# as14120_x31_usb.net
KiCad netlist of a schematic drawn in Altium Designer
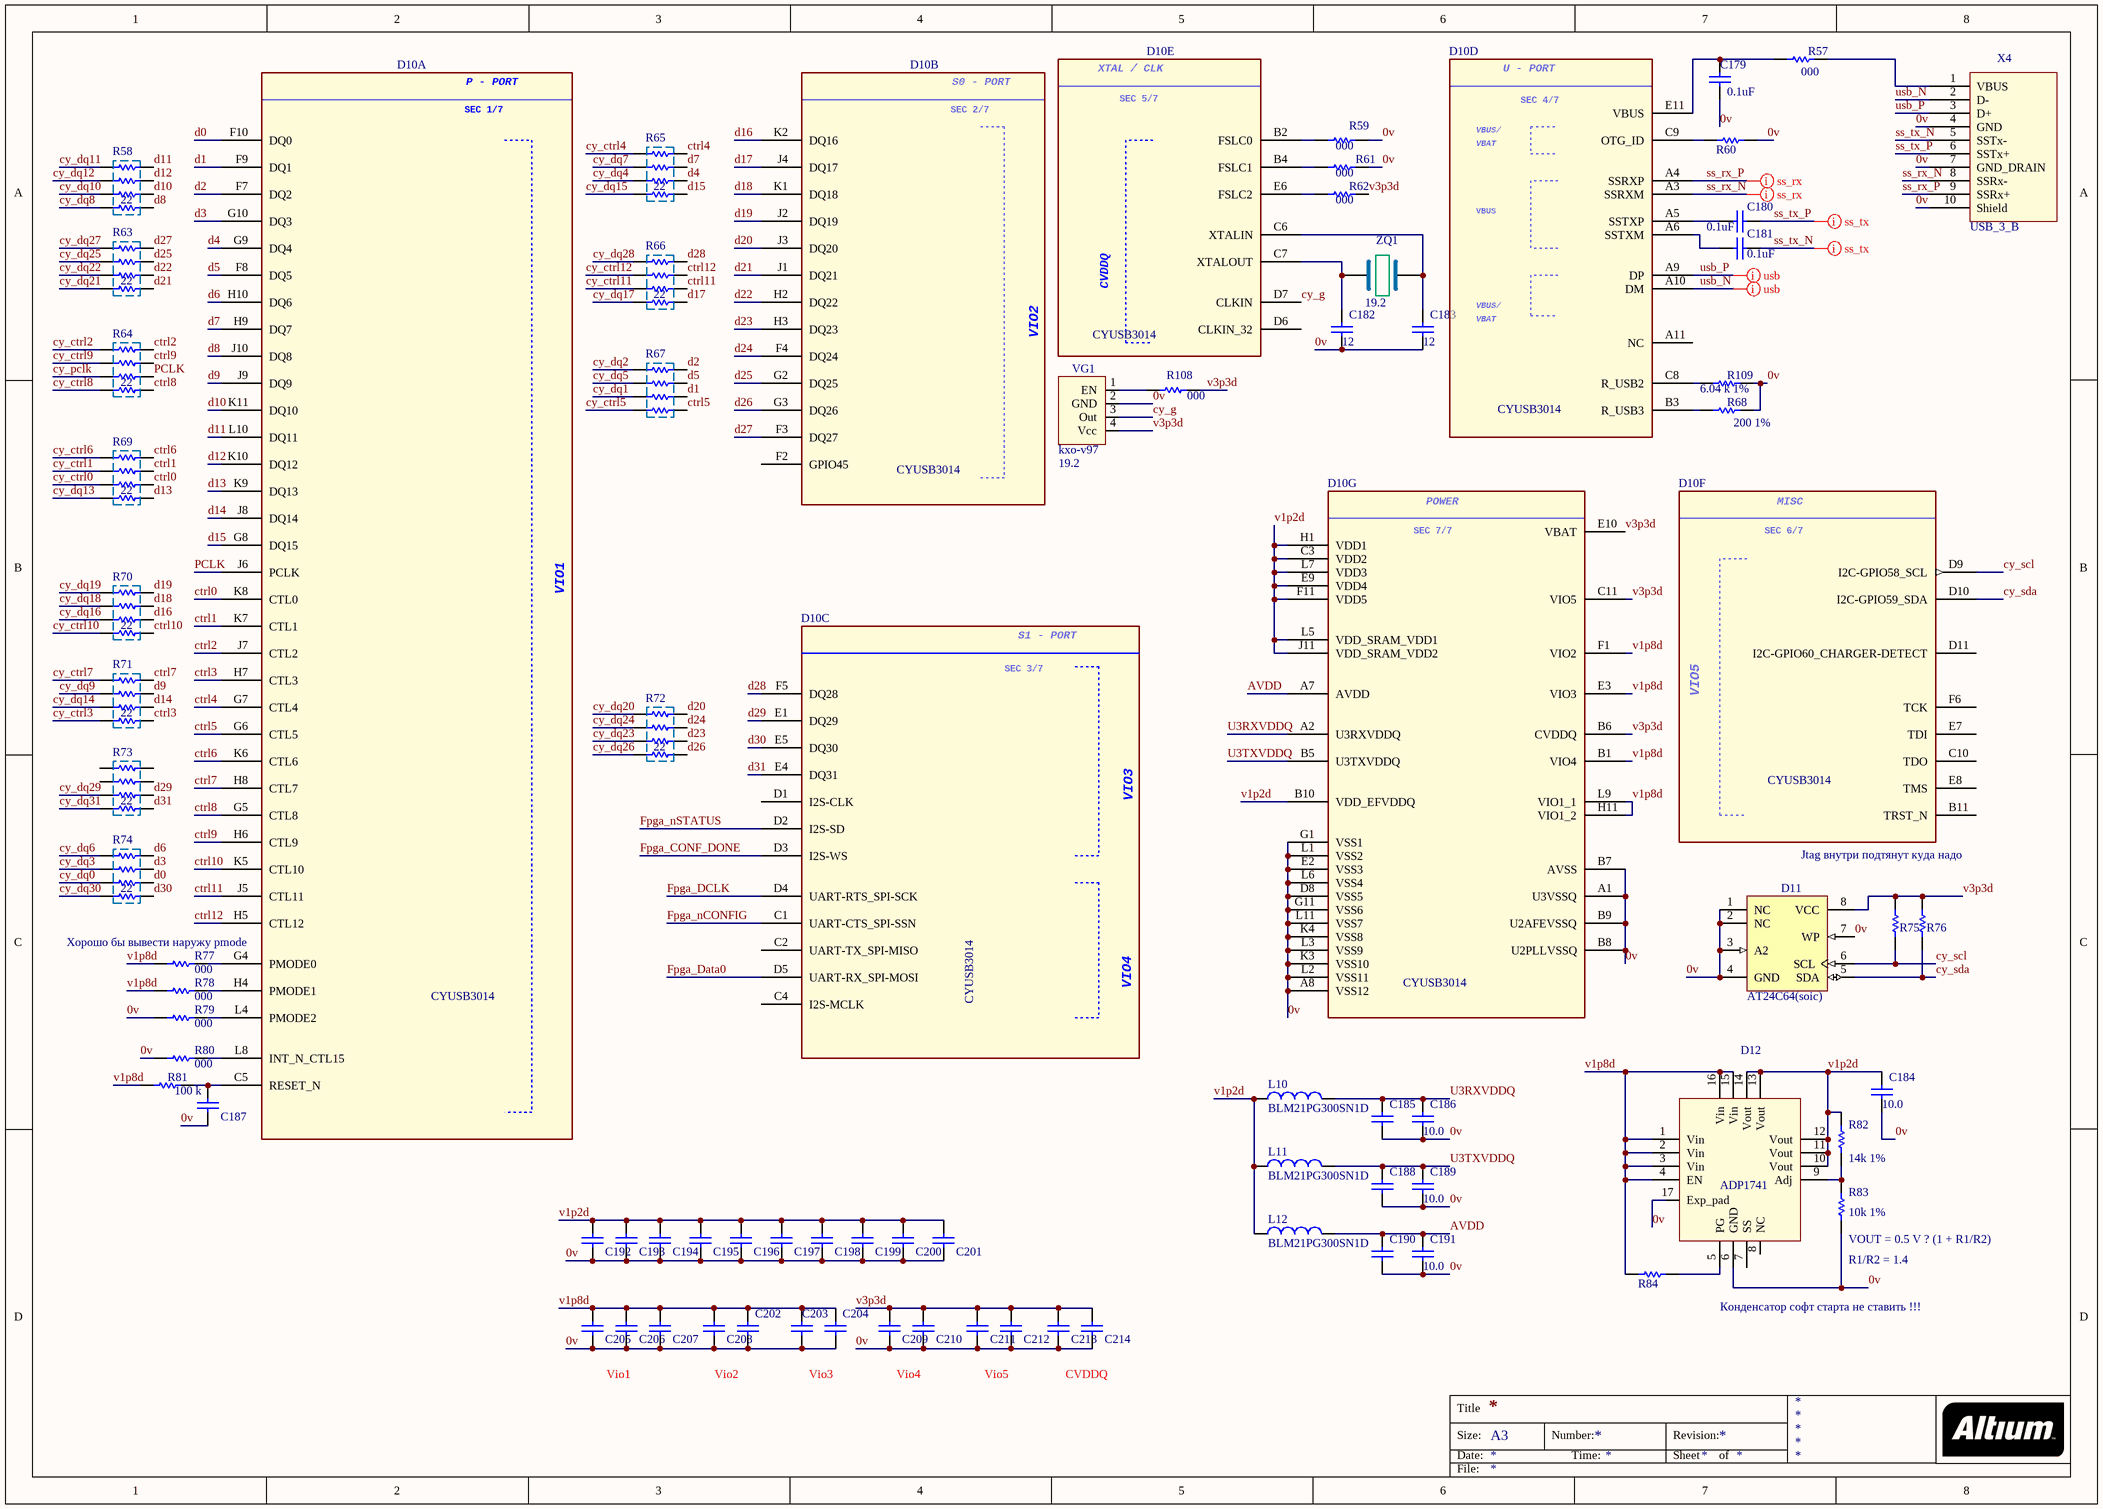
[diagram p0: as14120_x31_usb.SchDoc]

(export (version "E")
  (design (tool "Eeschema 10.0.6"))
  (components
    (comp (ref "C179")
      (value "0.1uF")
      (footprint "CAPC0402(1005)60_M")
      (description "CAP 1uF 10V ±20% 0402 (1005 Metric) Thickness 0.6mm SMD")
      (fields (field (name "TOLERANCE") "±20%") (field (name "Comment") "CAP 1uF 10V 0402(1005)"))
      (libsource (lib "as14120") (part "CAP_0402"))
    )
    (comp (ref "C180")
      (value "0.1uF")
      (footprint "CAPC0402(1005)60_M")
      (description "CAP 1uF 10V ±20% 0402 (1005 Metric) Thickness 0.6mm SMD")
      (fields (field (name "TOLERANCE") "±20%") (field (name "Comment") "CAP 1uF 10V 0402(1005)"))
      (libsource (lib "as14120") (part "CAP_0402"))
    )
    (comp (ref "C181")
      (value "0.1uF")
      (footprint "CAPC0402(1005)60_M")
      (description "CAP 1uF 10V ±20% 0402 (1005 Metric) Thickness 0.6mm SMD")
      (fields (field (name "TOLERANCE") "±20%") (field (name "Comment") "CAP 1uF 10V 0402(1005)"))
      (libsource (lib "as14120") (part "CAP_0402"))
    )
    (comp (ref "C182")
      (value "12")
      (footprint "CAPC0805(2012)100_N")
      (fields (field (name "Comment") "CAP_0805"))
      (libsource (lib "as14120") (part "CAP_0805"))
    )
    (comp (ref "C183")
      (value "12")
      (footprint "CAPC0805(2012)100_N")
      (fields (field (name "Comment") "CAP_0805"))
      (libsource (lib "as14120") (part "CAP_0805"))
    )
    (comp (ref "C184")
      (value "10.0")
      (footprint "CAPC0805(2012)100_N")
      (fields (field (name "Comment") "CAP_0805"))
      (libsource (lib "as14120") (part "CAP_0805"))
    )
    (comp (ref "C185")
      (value "CAP 1uF 10V 0402(1005)")
      (footprint "CAPC0402(1005)60_M")
      (description "CAP 1uF 10V ±20% 0402 (1005 Metric) Thickness 0.6mm SMD")
      (fields (field (name "TOLERANCE") "±20%"))
      (libsource (lib "as14120") (part "CAP_0402"))
    )
    (comp (ref "C186")
      (value "10.0")
      (footprint "CAPC0805(2012)100_N")
      (fields (field (name "Comment") "CAP_0805"))
      (libsource (lib "as14120") (part "CAP_0805"))
    )
    (comp (ref "C187")
      (value "CAP 1uF 10V 0402(1005)")
      (footprint "CAPC0402(1005)60_M")
      (description "CAP 1uF 10V ±20% 0402 (1005 Metric) Thickness 0.6mm SMD")
      (fields (field (name "TOLERANCE") "±20%"))
      (libsource (lib "as14120") (part "CAP_0402"))
    )
    (comp (ref "C188")
      (value "CAP 1uF 10V 0402(1005)")
      (footprint "CAPC0402(1005)60_M")
      (description "CAP 1uF 10V ±20% 0402 (1005 Metric) Thickness 0.6mm SMD")
      (fields (field (name "TOLERANCE") "±20%"))
      (libsource (lib "as14120") (part "CAP_0402"))
    )
    (comp (ref "C189")
      (value "10.0")
      (footprint "CAPC0805(2012)100_N")
      (fields (field (name "Comment") "CAP_0805"))
      (libsource (lib "as14120") (part "CAP_0805"))
    )
    (comp (ref "C190")
      (value "CAP 1uF 10V 0402(1005)")
      (footprint "CAPC0402(1005)60_M")
      (description "CAP 1uF 10V ±20% 0402 (1005 Metric) Thickness 0.6mm SMD")
      (fields (field (name "TOLERANCE") "±20%"))
      (libsource (lib "as14120") (part "CAP_0402"))
    )
    (comp (ref "C191")
      (value "10.0")
      (footprint "CAPC0805(2012)100_N")
      (fields (field (name "Comment") "CAP_0805"))
      (libsource (lib "as14120") (part "CAP_0805"))
    )
    (comp (ref "C192")
      (value "CAP 1uF 10V 0402(1005)")
      (footprint "CAPC0402(1005)60_M")
      (description "CAP 1uF 10V ±20% 0402 (1005 Metric) Thickness 0.6mm SMD")
      (fields (field (name "TOLERANCE") "±20%"))
      (libsource (lib "as14120") (part "CAP_0402"))
    )
    (comp (ref "C193")
      (value "CAP 1uF 10V 0402(1005)")
      (footprint "CAPC0402(1005)60_M")
      (description "CAP 1uF 10V ±20% 0402 (1005 Metric) Thickness 0.6mm SMD")
      (fields (field (name "TOLERANCE") "±20%"))
      (libsource (lib "as14120") (part "CAP_0402"))
    )
    (comp (ref "C194")
      (value "CAP 1uF 10V 0402(1005)")
      (footprint "CAPC0402(1005)60_M")
      (description "CAP 1uF 10V ±20% 0402 (1005 Metric) Thickness 0.6mm SMD")
      (fields (field (name "TOLERANCE") "±20%"))
      (libsource (lib "as14120") (part "CAP_0402"))
    )
    (comp (ref "C195")
      (value "CAP 1uF 10V 0402(1005)")
      (footprint "CAPC0402(1005)60_M")
      (description "CAP 1uF 10V ±20% 0402 (1005 Metric) Thickness 0.6mm SMD")
      (fields (field (name "TOLERANCE") "±20%"))
      (libsource (lib "as14120") (part "CAP_0402"))
    )
    (comp (ref "C196")
      (value "CAP 1uF 10V 0402(1005)")
      (footprint "CAPC0402(1005)60_M")
      (description "CAP 1uF 10V ±20% 0402 (1005 Metric) Thickness 0.6mm SMD")
      (fields (field (name "TOLERANCE") "±20%"))
      (libsource (lib "as14120") (part "CAP_0402"))
    )
    (comp (ref "C197")
      (value "CAP 1uF 10V 0402(1005)")
      (footprint "CAPC0402(1005)60_M")
      (description "CAP 1uF 10V ±20% 0402 (1005 Metric) Thickness 0.6mm SMD")
      (fields (field (name "TOLERANCE") "±20%"))
      (libsource (lib "as14120") (part "CAP_0402"))
    )
    (comp (ref "C198")
      (value "CAP 1uF 10V 0402(1005)")
      (footprint "CAPC0402(1005)60_M")
      (description "CAP 1uF 10V ±20% 0402 (1005 Metric) Thickness 0.6mm SMD")
      (fields (field (name "TOLERANCE") "±20%"))
      (libsource (lib "as14120") (part "CAP_0402"))
    )
    (comp (ref "C199")
      (value "CAP 1uF 10V 0402(1005)")
      (footprint "CAPC0402(1005)60_M")
      (description "CAP 1uF 10V ±20% 0402 (1005 Metric) Thickness 0.6mm SMD")
      (fields (field (name "TOLERANCE") "±20%"))
      (libsource (lib "as14120") (part "CAP_0402"))
    )
    (comp (ref "C200")
      (value "CAP 1uF 10V 0402(1005)")
      (footprint "CAPC0402(1005)60_M")
      (description "CAP 1uF 10V ±20% 0402 (1005 Metric) Thickness 0.6mm SMD")
      (fields (field (name "TOLERANCE") "±20%"))
      (libsource (lib "as14120") (part "CAP_0402"))
    )
    (comp (ref "C201")
      (value "CAP 1uF 10V 0402(1005)")
      (footprint "CAPC0402(1005)60_M")
      (description "CAP 1uF 10V ±20% 0402 (1005 Metric) Thickness 0.6mm SMD")
      (fields (field (name "TOLERANCE") "±20%"))
      (libsource (lib "as14120") (part "CAP_0402"))
    )
    (comp (ref "C202")
      (value "CAP 1uF 10V 0402(1005)")
      (footprint "CAPC0402(1005)60_M")
      (description "CAP 1uF 10V ±20% 0402 (1005 Metric) Thickness 0.6mm SMD")
      (fields (field (name "TOLERANCE") "±20%"))
      (libsource (lib "as14120") (part "CAP_0402"))
    )
    (comp (ref "C203")
      (value "CAP 1uF 10V 0402(1005)")
      (footprint "CAPC0402(1005)60_M")
      (description "CAP 1uF 10V ±20% 0402 (1005 Metric) Thickness 0.6mm SMD")
      (fields (field (name "TOLERANCE") "±20%"))
      (libsource (lib "as14120") (part "CAP_0402"))
    )
    (comp (ref "C204")
      (value "CAP 1uF 10V 0402(1005)")
      (footprint "CAPC0402(1005)60_M")
      (description "CAP 1uF 10V ±20% 0402 (1005 Metric) Thickness 0.6mm SMD")
      (fields (field (name "TOLERANCE") "±20%"))
      (libsource (lib "as14120") (part "CAP_0402"))
    )
    (comp (ref "C205")
      (value "CAP 1uF 10V 0402(1005)")
      (footprint "CAPC0402(1005)60_M")
      (description "CAP 1uF 10V ±20% 0402 (1005 Metric) Thickness 0.6mm SMD")
      (fields (field (name "TOLERANCE") "±20%"))
      (libsource (lib "as14120") (part "CAP_0402"))
    )
    (comp (ref "C206")
      (value "CAP 1uF 10V 0402(1005)")
      (footprint "CAPC0402(1005)60_M")
      (description "CAP 1uF 10V ±20% 0402 (1005 Metric) Thickness 0.6mm SMD")
      (fields (field (name "TOLERANCE") "±20%"))
      (libsource (lib "as14120") (part "CAP_0402"))
    )
    (comp (ref "C207")
      (value "CAP 1uF 10V 0402(1005)")
      (footprint "CAPC0402(1005)60_M")
      (description "CAP 1uF 10V ±20% 0402 (1005 Metric) Thickness 0.6mm SMD")
      (fields (field (name "TOLERANCE") "±20%"))
      (libsource (lib "as14120") (part "CAP_0402"))
    )
    (comp (ref "C208")
      (value "CAP 1uF 10V 0402(1005)")
      (footprint "CAPC0402(1005)60_M")
      (description "CAP 1uF 10V ±20% 0402 (1005 Metric) Thickness 0.6mm SMD")
      (fields (field (name "TOLERANCE") "±20%"))
      (libsource (lib "as14120") (part "CAP_0402"))
    )
    (comp (ref "C209")
      (value "CAP 1uF 10V 0402(1005)")
      (footprint "CAPC0402(1005)60_M")
      (description "CAP 1uF 10V ±20% 0402 (1005 Metric) Thickness 0.6mm SMD")
      (fields (field (name "TOLERANCE") "±20%"))
      (libsource (lib "as14120") (part "CAP_0402"))
    )
    (comp (ref "C210")
      (value "CAP 1uF 10V 0402(1005)")
      (footprint "CAPC0402(1005)60_M")
      (description "CAP 1uF 10V ±20% 0402 (1005 Metric) Thickness 0.6mm SMD")
      (fields (field (name "TOLERANCE") "±20%"))
      (libsource (lib "as14120") (part "CAP_0402"))
    )
    (comp (ref "C211")
      (value "CAP 1uF 10V 0402(1005)")
      (footprint "CAPC0402(1005)60_M")
      (description "CAP 1uF 10V ±20% 0402 (1005 Metric) Thickness 0.6mm SMD")
      (fields (field (name "TOLERANCE") "±20%"))
      (libsource (lib "as14120") (part "CAP_0402"))
    )
    (comp (ref "C212")
      (value "CAP 1uF 10V 0402(1005)")
      (footprint "CAPC0402(1005)60_M")
      (description "CAP 1uF 10V ±20% 0402 (1005 Metric) Thickness 0.6mm SMD")
      (fields (field (name "TOLERANCE") "±20%"))
      (libsource (lib "as14120") (part "CAP_0402"))
    )
    (comp (ref "C213")
      (value "CAP 1uF 10V 0402(1005)")
      (footprint "CAPC0402(1005)60_M")
      (description "CAP 1uF 10V ±20% 0402 (1005 Metric) Thickness 0.6mm SMD")
      (fields (field (name "TOLERANCE") "±20%"))
      (libsource (lib "as14120") (part "CAP_0402"))
    )
    (comp (ref "C214")
      (value "CAP 1uF 10V 0402(1005)")
      (footprint "CAPC0402(1005)60_M")
      (description "CAP 1uF 10V ±20% 0402 (1005 Metric) Thickness 0.6mm SMD")
      (fields (field (name "TOLERANCE") "±20%"))
      (libsource (lib "as14120") (part "CAP_0402"))
    )
    (comp (ref "D10")
      (value "CYUSB3014")
      (footprint "BGA121C80P11X11")
      (libsource (lib "") (part "CYUSB3014-BZXC_1"))
    )
    (comp (ref "D11")
      (value "AT24C64(soic)")
      (footprint "8S1_N")
      (libsource (lib "Atmel Serial EEPROM") (part "AT24C08BN-SP25-T"))
    )
    (comp (ref "D12") (value "ADP1741") (footprint "CP-16-4_N") (libsource (lib "as14120") (part "ADP1741")))
    (comp (ref "L10")
      (value "BLM21PG300SN1D")
      (footprint "CAPC0805(2012)100_N")
      (libsource (lib "as14120") (part "Ferrite_beat"))
    )
    (comp (ref "L11")
      (value "BLM21PG300SN1D")
      (footprint "CAPC0805(2012)100_N")
      (libsource (lib "as14120") (part "Ferrite_beat"))
    )
    (comp (ref "L12")
      (value "BLM21PG300SN1D")
      (footprint "CAPC0805(2012)100_N")
      (libsource (lib "as14120") (part "Ferrite_beat"))
    )
    (comp (ref "R57")
      (value "000")
      (footprint "RESC0805(2012)_L")
      (description "1K 0.125W 1% 0805 (2012 Metric)  SMD")
      (fields (field (name "TOLERANCE") "1 %") (field (name "POWER") "0.125 W"))
      (libsource (lib "as14120") (part "RES_0805"))
    )
    (comp (ref "R58") (value "22") (footprint "CAY16") (libsource (lib "as14120") (part "cay16-J4")))
    (comp (ref "R59")
      (value "000")
      (footprint "RESC0603(1608)_L")
      (description "1K 0.1W 5% 0603 (1608 Metric)  SMD")
      (fields (field (name "TOLERANCE") "5 %") (field (name "POWER") "0.1 W"))
      (libsource (lib "as14120") (part "RES_0603"))
    )
    (comp (ref "R60")
      (value "???")
      (footprint "RESC0603(1608)_L")
      (description "1K 0.1W 5% 0603 (1608 Metric)  SMD")
      (fields (field (name "TOLERANCE") "5 %") (field (name "POWER") "0.1 W"))
      (libsource (lib "as14120") (part "RES_0603"))
    )
    (comp (ref "R61")
      (value "000")
      (footprint "RESC0603(1608)_L")
      (description "1K 0.1W 5% 0603 (1608 Metric)  SMD")
      (fields (field (name "TOLERANCE") "5 %") (field (name "POWER") "0.1 W"))
      (libsource (lib "as14120") (part "RES_0603"))
    )
    (comp (ref "R62")
      (value "000")
      (footprint "RESC0603(1608)_L")
      (description "1K 0.1W 5% 0603 (1608 Metric)  SMD")
      (fields (field (name "TOLERANCE") "5 %") (field (name "POWER") "0.1 W"))
      (libsource (lib "as14120") (part "RES_0603"))
    )
    (comp (ref "R63") (value "22") (footprint "CAY16") (libsource (lib "as14120") (part "cay16-J4")))
    (comp (ref "R64") (value "22") (footprint "CAY16") (libsource (lib "as14120") (part "cay16-J4")))
    (comp (ref "R65") (value "22") (footprint "CAY16") (libsource (lib "as14120") (part "cay16-J4")))
    (comp (ref "R66") (value "22") (footprint "CAY16") (libsource (lib "as14120") (part "cay16-J4")))
    (comp (ref "R67") (value "~") (footprint "CAY16") (libsource (lib "as14120") (part "cay16-J4")))
    (comp (ref "R68")
      (value "200 1%")
      (footprint "RESC0805(2012)_L")
      (description "1K 0.125W 1% 0805 (2012 Metric)  SMD")
      (fields (field (name "TOLERANCE") "1 %") (field (name "POWER") "0.125 W"))
      (libsource (lib "as14120") (part "RES_0805"))
    )
    (comp (ref "R69") (value "22") (footprint "CAY16") (libsource (lib "as14120") (part "cay16-J4")))
    (comp (ref "R70") (value "22") (footprint "CAY16") (libsource (lib "as14120") (part "cay16-J4")))
    (comp (ref "R71") (value "22") (footprint "CAY16") (libsource (lib "as14120") (part "cay16-J4")))
    (comp (ref "R72") (value "22") (footprint "CAY16") (libsource (lib "as14120") (part "cay16-J4")))
    (comp (ref "R73") (value "22") (footprint "CAY16") (libsource (lib "as14120") (part "cay16-J4")))
    (comp (ref "R74") (value "22") (footprint "CAY16") (libsource (lib "as14120") (part "cay16-J4")))
    (comp (ref "R75")
      (value "1K 5% 0603(1608)")
      (footprint "RESC0603(1608)_L")
      (description "1K 0.1W 5% 0603 (1608 Metric)  SMD")
      (fields (field (name "TOLERANCE") "5 %") (field (name "POWER") "0.1 W"))
      (libsource (lib "as14120") (part "RES_0603"))
    )
    (comp (ref "R76")
      (value "1K 5% 0603(1608)")
      (footprint "RESC0603(1608)_L")
      (description "1K 0.1W 5% 0603 (1608 Metric)  SMD")
      (fields (field (name "TOLERANCE") "5 %") (field (name "POWER") "0.1 W"))
      (libsource (lib "as14120") (part "RES_0603"))
    )
    (comp (ref "R77")
      (value "000")
      (footprint "RESC0603(1608)_L")
      (description "1K 0.1W 5% 0603 (1608 Metric)  SMD")
      (fields (field (name "TOLERANCE") "5 %") (field (name "POWER") "0.1 W"))
      (libsource (lib "as14120") (part "RES_0603"))
    )
    (comp (ref "R78")
      (value "000")
      (footprint "RESC0603(1608)_L")
      (description "1K 0.1W 5% 0603 (1608 Metric)  SMD")
      (fields (field (name "TOLERANCE") "5 %") (field (name "POWER") "0.1 W"))
      (libsource (lib "as14120") (part "RES_0603"))
    )
    (comp (ref "R79")
      (value "000")
      (footprint "RESC0603(1608)_L")
      (description "1K 0.1W 5% 0603 (1608 Metric)  SMD")
      (fields (field (name "TOLERANCE") "5 %") (field (name "POWER") "0.1 W"))
      (libsource (lib "as14120") (part "RES_0603"))
    )
    (comp (ref "R80")
      (value "000")
      (footprint "RESC0603(1608)_L")
      (description "1K 0.1W 5% 0603 (1608 Metric)  SMD")
      (fields (field (name "TOLERANCE") "5 %") (field (name "POWER") "0.1 W"))
      (libsource (lib "as14120") (part "RES_0603"))
    )
    (comp (ref "R81")
      (value "100 k")
      (footprint "RESC0603(1608)_L")
      (description "1K 0.1W 5% 0603 (1608 Metric)  SMD")
      (fields (field (name "TOLERANCE") "5 %") (field (name "POWER") "0.1 W"))
      (libsource (lib "as14120") (part "RES_0603"))
    )
    (comp (ref "R82")
      (value "14k 1%")
      (footprint "RESC0805(2012)_L")
      (description "1K 0.125W 1% 0805 (2012 Metric)  SMD")
      (fields (field (name "TOLERANCE") "1 %") (field (name "POWER") "0.125 W"))
      (libsource (lib "as14120") (part "RES_0805"))
    )
    (comp (ref "R83")
      (value "10k 1%")
      (footprint "RESC0805(2012)_L")
      (description "1K 0.125W 1% 0805 (2012 Metric)  SMD")
      (fields (field (name "TOLERANCE") "1 %") (field (name "POWER") "0.125 W"))
      (libsource (lib "as14120") (part "RES_0805"))
    )
    (comp (ref "R84")
      (value "1K 5% 0603(1608)")
      (footprint "RESC0603(1608)_L")
      (description "1K 0.1W 5% 0603 (1608 Metric)  SMD")
      (fields (field (name "TOLERANCE") "5 %") (field (name "POWER") "0.1 W"))
      (libsource (lib "as14120") (part "RES_0603"))
    )
    (comp (ref "R108")
      (value "000")
      (footprint "RESC0603(1608)_L")
      (description "1K 0.1W 5% 0603 (1608 Metric)  SMD")
      (fields (field (name "TOLERANCE") "5 %") (field (name "POWER") "0.1 W"))
      (libsource (lib "as14120") (part "RES_0603"))
    )
    (comp (ref "R109")
      (value "6.04 k 1%")
      (footprint "RESC0805(2012)_L")
      (description "1K 0.125W 1% 0805 (2012 Metric)  SMD")
      (fields (field (name "TOLERANCE") "1 %") (field (name "POWER") "0.125 W"))
      (libsource (lib "as14120") (part "RES_0805"))
    )
    (comp (ref "VG1")
      (value "kxo-v97")
      (footprint "kxo-v97")
      (fields (field (name "ALTIUM_VALUE") "19.2"))
      (libsource (lib "as14120") (part "kxo-v97"))
    )
    (comp (ref "X4") (value "USB_3_B") (footprint "USB3_B") (libsource (lib "as14120") (part "USB_3_B")))
    (comp (ref "ZQ1")
      (value "19.2")
      (footprint "BCY-W2/E4.7")
      (fields (field (name "Comment") "Resonator"))
      (libsource (lib "as14120") (part "Resonator"))
    )
  )
  (nets
    (net (code "1") (name "/0v") (class "Default")
      (node (ref "C179") (pin "2") (pinfunction "2_2") (pintype "passive"))
      (node (ref "C182") (pin "1") (pinfunction "1_1") (pintype "passive"))
      (node (ref "C183") (pin "1") (pinfunction "1_1") (pintype "passive"))
      (node (ref "C184") (pin "1") (pinfunction "1_1") (pintype "passive"))
      (node (ref "C185") (pin "1") (pinfunction "1_1") (pintype "passive"))
      (node (ref "C186") (pin "1") (pinfunction "1_1") (pintype "passive"))
      (node (ref "C187") (pin "1") (pinfunction "1_1") (pintype "passive"))
      (node (ref "C188") (pin "1") (pinfunction "1_1") (pintype "passive"))
      (node (ref "C189") (pin "1") (pinfunction "1_1") (pintype "passive"))
      (node (ref "C190") (pin "1") (pinfunction "1_1") (pintype "passive"))
      (node (ref "C191") (pin "1") (pinfunction "1_1") (pintype "passive"))
      (node (ref "C192") (pin "1") (pinfunction "1_1") (pintype "passive"))
      (node (ref "C193") (pin "1") (pinfunction "1_1") (pintype "passive"))
      (node (ref "C194") (pin "1") (pinfunction "1_1") (pintype "passive"))
      (node (ref "C195") (pin "1") (pinfunction "1_1") (pintype "passive"))
      (node (ref "C196") (pin "1") (pinfunction "1_1") (pintype "passive"))
      (node (ref "C197") (pin "1") (pinfunction "1_1") (pintype "passive"))
      (node (ref "C198") (pin "1") (pinfunction "1_1") (pintype "passive"))
      (node (ref "C199") (pin "1") (pinfunction "1_1") (pintype "passive"))
      (node (ref "C200") (pin "1") (pinfunction "1_1") (pintype "passive"))
      (node (ref "C201") (pin "1") (pinfunction "1_1") (pintype "passive"))
      (node (ref "C202") (pin "1") (pinfunction "1_1") (pintype "passive"))
      (node (ref "C203") (pin "1") (pinfunction "1_1") (pintype "passive"))
      (node (ref "C204") (pin "1") (pinfunction "1_1") (pintype "passive"))
      (node (ref "C205") (pin "1") (pinfunction "1_1") (pintype "passive"))
      (node (ref "C206") (pin "1") (pinfunction "1_1") (pintype "passive"))
      (node (ref "C207") (pin "1") (pinfunction "1_1") (pintype "passive"))
      (node (ref "C208") (pin "1") (pinfunction "1_1") (pintype "passive"))
      (node (ref "C209") (pin "1") (pinfunction "1_1") (pintype "passive"))
      (node (ref "C210") (pin "1") (pinfunction "1_1") (pintype "passive"))
      (node (ref "C211") (pin "1") (pinfunction "1_1") (pintype "passive"))
      (node (ref "C212") (pin "1") (pinfunction "1_1") (pintype "passive"))
      (node (ref "C213") (pin "1") (pinfunction "1_1") (pintype "passive"))
      (node (ref "C214") (pin "1") (pinfunction "1_1") (pintype "passive"))
      (node (ref "D10") (pin "A1") (pinfunction "U3VSSQ_A1") (pintype "passive"))
      (node (ref "D10") (pin "A8") (pinfunction "VSS12_A8") (pintype "passive"))
      (node (ref "D10") (pin "B7") (pinfunction "AVSS_B7") (pintype "passive"))
      (node (ref "D10") (pin "B8") (pinfunction "U2PLLVSSQ_B8") (pintype "passive"))
      (node (ref "D10") (pin "B9") (pinfunction "U2AFEVSSQ_B9") (pintype "passive"))
      (node (ref "D10") (pin "D8") (pinfunction "VSS5_D8") (pintype "passive"))
      (node (ref "D10") (pin "E2") (pinfunction "VSS3_E2") (pintype "passive"))
      (node (ref "D10") (pin "G1") (pinfunction "VSS1_G1") (pintype "passive"))
      (node (ref "D10") (pin "G11") (pinfunction "VSS6_G11") (pintype "passive"))
      (node (ref "D10") (pin "K3") (pinfunction "VSS10_K3") (pintype "passive"))
      (node (ref "D10") (pin "K4") (pinfunction "VSS8_K4") (pintype "passive"))
      (node (ref "D10") (pin "L1") (pinfunction "VSS2_L1") (pintype "passive"))
      (node (ref "D10") (pin "L11") (pinfunction "VSS7_L11") (pintype "passive"))
      (node (ref "D10") (pin "L2") (pinfunction "VSS11_L2") (pintype "passive"))
      (node (ref "D10") (pin "L3") (pinfunction "VSS9_L3") (pintype "passive"))
      (node (ref "D10") (pin "L6") (pinfunction "VSS4_L6") (pintype "passive"))
      (node (ref "D11") (pin "1") (pinfunction "NC_1") (pintype "passive"))
      (node (ref "D11") (pin "2") (pinfunction "NC_2") (pintype "passive"))
      (node (ref "D11") (pin "3") (pinfunction "A2_3") (pintype "input"))
      (node (ref "D11") (pin "4") (pinfunction "GND_4") (pintype "power_in"))
      (node (ref "D11") (pin "7") (pinfunction "WP_7") (pintype "input"))
      (node (ref "D12") (pin "17") (pinfunction "Exp_pad_17") (pintype "passive"))
      (node (ref "D12") (pin "6") (pinfunction "GND_6") (pintype "passive"))
      (node (ref "R109") (pin "2") (pinfunction "2_2") (pintype "passive"))
      (node (ref "R59") (pin "1") (pinfunction "1_1") (pintype "passive"))
      (node (ref "R60") (pin "2") (pinfunction "2_2") (pintype "passive"))
      (node (ref "R61") (pin "1") (pinfunction "1_1") (pintype "passive"))
      (node (ref "R68") (pin "2") (pinfunction "2_2") (pintype "passive"))
      (node (ref "R79") (pin "2") (pinfunction "2_2") (pintype "passive"))
      (node (ref "R80") (pin "2") (pinfunction "2_2") (pintype "passive"))
      (node (ref "R83") (pin "1") (pinfunction "1_1") (pintype "passive"))
      (node (ref "VG1") (pin "2") (pinfunction "GND_2") (pintype "passive"))
      (node (ref "X4") (pin "10") (pinfunction "Shield_10") (pintype "passive"))
      (node (ref "X4") (pin "4") (pinfunction "GND_4") (pintype "passive"))
      (node (ref "X4") (pin "7") (pinfunction "GND_DRAIN_7") (pintype "passive"))
    )
    (net (code "2") (name "/AVDD") (class "Default")
      (node (ref "C190") (pin "2") (pinfunction "2_2") (pintype "passive"))
      (node (ref "C191") (pin "2") (pinfunction "2_2") (pintype "passive"))
      (node (ref "D10") (pin "A7") (pinfunction "AVDD_A7") (pintype "passive"))
      (node (ref "L12") (pin "2") (pinfunction "2_2") (pintype "passive"))
    )
    (net (code "3") (name "/Fpga_CONF_DONE") (class "Default")
      (node (ref "D10") (pin "D3") (pinfunction "I2S-WS_D3") (pintype "passive"))
    )
    (net (code "4") (name "/Fpga_DCLK") (class "Default")
      (node (ref "D10") (pin "D4") (pinfunction "UART-RTS_SPI-SCK_D4") (pintype "passive"))
    )
    (net (code "5") (name "/Fpga_Data0") (class "Default")
      (node (ref "D10") (pin "D5") (pinfunction "UART-RX_SPI-MOSI_D5") (pintype "passive"))
    )
    (net (code "6") (name "/Fpga_nCONFIG") (class "Default")
      (node (ref "D10") (pin "C1") (pinfunction "UART-CTS_SPI-SSN_C1") (pintype "passive"))
    )
    (net (code "7") (name "/Fpga_nSTATUS") (class "Default")
      (node (ref "D10") (pin "D2") (pinfunction "I2S-SD_D2") (pintype "passive"))
    )
    (net (code "8") (name "/PCLK") (class "Default")
      (node (ref "D10") (pin "J6") (pinfunction "PCLK_J6") (pintype "passive"))
      (node (ref "R64") (pin "6") (pinfunction "6_6") (pintype "passive"))
    )
    (net (code "9") (name "/U3RXVDDQ") (class "Default")
      (node (ref "C185") (pin "2") (pinfunction "2_2") (pintype "passive"))
      (node (ref "C186") (pin "2") (pinfunction "2_2") (pintype "passive"))
      (node (ref "D10") (pin "A2") (pinfunction "U3RXVDDQ_A2") (pintype "passive"))
      (node (ref "L10") (pin "2") (pinfunction "2_2") (pintype "passive"))
    )
    (net (code "10") (name "/U3TXVDDQ") (class "Default")
      (node (ref "C188") (pin "2") (pinfunction "2_2") (pintype "passive"))
      (node (ref "C189") (pin "2") (pinfunction "2_2") (pintype "passive"))
      (node (ref "D10") (pin "B5") (pinfunction "U3TXVDDQ_B5") (pintype "passive"))
      (node (ref "L11") (pin "2") (pinfunction "2_2") (pintype "passive"))
    )
    (net (code "11") (name "/ctrl0") (class "Default")
      (node (ref "D10") (pin "K8") (pinfunction "CTL0_K8") (pintype "passive"))
      (node (ref "R69") (pin "6") (pinfunction "6_6") (pintype "passive"))
    )
    (net (code "12") (name "/ctrl1") (class "Default")
      (node (ref "D10") (pin "K7") (pinfunction "CTL1_K7") (pintype "passive"))
      (node (ref "R69") (pin "7") (pinfunction "7_7") (pintype "passive"))
    )
    (net (code "13") (name "/ctrl2") (class "Default")
      (node (ref "D10") (pin "J7") (pinfunction "CTL2_J7") (pintype "passive"))
      (node (ref "R64") (pin "8") (pinfunction "8_8") (pintype "passive"))
    )
    (net (code "14") (name "/ctrl3") (class "Default")
      (node (ref "D10") (pin "H7") (pinfunction "CTL3_H7") (pintype "passive"))
      (node (ref "R71") (pin "5") (pinfunction "5_5") (pintype "passive"))
    )
    (net (code "15") (name "/ctrl4") (class "Default")
      (node (ref "D10") (pin "G7") (pinfunction "CTL4_G7") (pintype "passive"))
      (node (ref "R65") (pin "8") (pinfunction "8_8") (pintype "passive"))
    )
    (net (code "16") (name "/ctrl5") (class "Default")
      (node (ref "D10") (pin "G6") (pinfunction "CTL5_G6") (pintype "passive"))
      (node (ref "R67") (pin "5") (pinfunction "5_5") (pintype "passive"))
    )
    (net (code "17") (name "/ctrl6") (class "Default")
      (node (ref "D10") (pin "K6") (pinfunction "CTL6_K6") (pintype "passive"))
      (node (ref "R69") (pin "8") (pinfunction "8_8") (pintype "passive"))
    )
    (net (code "18") (name "/ctrl7") (class "Default")
      (node (ref "D10") (pin "H8") (pinfunction "CTL7_H8") (pintype "passive"))
      (node (ref "R71") (pin "8") (pinfunction "8_8") (pintype "passive"))
    )
    (net (code "19") (name "/ctrl8") (class "Default")
      (node (ref "D10") (pin "G5") (pinfunction "CTL8_G5") (pintype "passive"))
      (node (ref "R64") (pin "5") (pinfunction "5_5") (pintype "passive"))
    )
    (net (code "20") (name "/ctrl9") (class "Default")
      (node (ref "D10") (pin "H6") (pinfunction "CTL9_H6") (pintype "passive"))
      (node (ref "R64") (pin "7") (pinfunction "7_7") (pintype "passive"))
    )
    (net (code "21") (name "/ctrl10") (class "Default")
      (node (ref "D10") (pin "K5") (pinfunction "CTL10_K5") (pintype "passive"))
      (node (ref "R70") (pin "5") (pinfunction "5_5") (pintype "passive"))
    )
    (net (code "22") (name "/ctrl11") (class "Default")
      (node (ref "D10") (pin "J5") (pinfunction "CTL11_J5") (pintype "passive"))
      (node (ref "R66") (pin "6") (pinfunction "6_6") (pintype "passive"))
    )
    (net (code "23") (name "/ctrl12") (class "Default")
      (node (ref "D10") (pin "H5") (pinfunction "CTL12_H5") (pintype "passive"))
      (node (ref "R66") (pin "7") (pinfunction "7_7") (pintype "passive"))
    )
    (net (code "24") (name "/cy_ctrl0") (class "Default")
      (node (ref "R69") (pin "3") (pinfunction "3_3") (pintype "passive"))
    )
    (net (code "25") (name "/cy_ctrl1") (class "Default")
      (node (ref "R69") (pin "2") (pinfunction "2_2") (pintype "passive"))
    )
    (net (code "26") (name "/cy_ctrl2") (class "Default")
      (node (ref "R64") (pin "1") (pinfunction "1_1") (pintype "passive"))
    )
    (net (code "27") (name "/cy_ctrl3") (class "Default")
      (node (ref "R71") (pin "4") (pinfunction "4_4") (pintype "passive"))
    )
    (net (code "28") (name "/cy_ctrl4") (class "Default")
      (node (ref "R65") (pin "1") (pinfunction "1_1") (pintype "passive"))
    )
    (net (code "29") (name "/cy_ctrl5") (class "Default")
      (node (ref "R67") (pin "4") (pinfunction "4_4") (pintype "passive"))
    )
    (net (code "30") (name "/cy_ctrl6") (class "Default")
      (node (ref "R69") (pin "1") (pinfunction "1_1") (pintype "passive"))
    )
    (net (code "31") (name "/cy_ctrl7") (class "Default")
      (node (ref "R71") (pin "1") (pinfunction "1_1") (pintype "passive"))
    )
    (net (code "32") (name "/cy_ctrl8") (class "Default")
      (node (ref "R64") (pin "4") (pinfunction "4_4") (pintype "passive"))
    )
    (net (code "33") (name "/cy_ctrl9") (class "Default")
      (node (ref "R64") (pin "2") (pinfunction "2_2") (pintype "passive"))
    )
    (net (code "34") (name "/cy_ctrl10") (class "Default")
      (node (ref "R70") (pin "4") (pinfunction "4_4") (pintype "passive"))
    )
    (net (code "35") (name "/cy_ctrl11") (class "Default")
      (node (ref "R66") (pin "3") (pinfunction "3_3") (pintype "passive"))
    )
    (net (code "36") (name "/cy_ctrl12") (class "Default")
      (node (ref "R66") (pin "2") (pinfunction "2_2") (pintype "passive"))
    )
    (net (code "37") (name "/cy_dq0") (class "Default")
      (node (ref "R74") (pin "3") (pinfunction "3_3") (pintype "passive"))
    )
    (net (code "38") (name "/cy_dq1") (class "Default")
      (node (ref "R67") (pin "3") (pinfunction "3_3") (pintype "passive"))
    )
    (net (code "39") (name "/cy_dq2") (class "Default")
      (node (ref "R67") (pin "1") (pinfunction "1_1") (pintype "passive"))
    )
    (net (code "40") (name "/cy_dq3") (class "Default")
      (node (ref "R74") (pin "2") (pinfunction "2_2") (pintype "passive"))
    )
    (net (code "41") (name "/cy_dq4") (class "Default")
      (node (ref "R65") (pin "3") (pinfunction "3_3") (pintype "passive"))
    )
    (net (code "42") (name "/cy_dq5") (class "Default")
      (node (ref "R67") (pin "2") (pinfunction "2_2") (pintype "passive"))
    )
    (net (code "43") (name "/cy_dq6") (class "Default")
      (node (ref "R74") (pin "1") (pinfunction "1_1") (pintype "passive"))
    )
    (net (code "44") (name "/cy_dq7") (class "Default")
      (node (ref "R65") (pin "2") (pinfunction "2_2") (pintype "passive"))
    )
    (net (code "45") (name "/cy_dq8") (class "Default")
      (node (ref "R58") (pin "4") (pinfunction "4_4") (pintype "passive"))
    )
    (net (code "46") (name "/cy_dq9") (class "Default")
      (node (ref "R71") (pin "2") (pinfunction "2_2") (pintype "passive"))
    )
    (net (code "47") (name "/cy_dq10") (class "Default")
      (node (ref "R58") (pin "3") (pinfunction "3_3") (pintype "passive"))
    )
    (net (code "48") (name "/cy_dq11") (class "Default")
      (node (ref "R58") (pin "1") (pinfunction "1_1") (pintype "passive"))
    )
    (net (code "49") (name "/cy_dq12") (class "Default")
      (node (ref "R58") (pin "2") (pinfunction "2_2") (pintype "passive"))
    )
    (net (code "50") (name "/cy_dq13") (class "Default")
      (node (ref "R69") (pin "4") (pinfunction "4_4") (pintype "passive"))
    )
    (net (code "51") (name "/cy_dq14") (class "Default")
      (node (ref "R71") (pin "3") (pinfunction "3_3") (pintype "passive"))
    )
    (net (code "52") (name "/cy_dq15") (class "Default")
      (node (ref "R65") (pin "4") (pinfunction "4_4") (pintype "passive"))
    )
    (net (code "53") (name "/cy_dq16") (class "Default")
      (node (ref "R70") (pin "3") (pinfunction "3_3") (pintype "passive"))
    )
    (net (code "54") (name "/cy_dq17") (class "Default")
      (node (ref "R66") (pin "4") (pinfunction "4_4") (pintype "passive"))
    )
    (net (code "55") (name "/cy_dq18") (class "Default")
      (node (ref "R70") (pin "2") (pinfunction "2_2") (pintype "passive"))
    )
    (net (code "56") (name "/cy_dq19") (class "Default")
      (node (ref "R70") (pin "1") (pinfunction "1_1") (pintype "passive"))
    )
    (net (code "57") (name "/cy_dq20") (class "Default")
      (node (ref "R72") (pin "1") (pinfunction "1_1") (pintype "passive"))
    )
    (net (code "58") (name "/cy_dq21") (class "Default")
      (node (ref "R63") (pin "4") (pinfunction "4_4") (pintype "passive"))
    )
    (net (code "59") (name "/cy_dq22") (class "Default")
      (node (ref "R63") (pin "3") (pinfunction "3_3") (pintype "passive"))
    )
    (net (code "60") (name "/cy_dq23") (class "Default")
      (node (ref "R72") (pin "3") (pinfunction "3_3") (pintype "passive"))
    )
    (net (code "61") (name "/cy_dq24") (class "Default")
      (node (ref "R72") (pin "2") (pinfunction "2_2") (pintype "passive"))
    )
    (net (code "62") (name "/cy_dq25") (class "Default")
      (node (ref "R63") (pin "2") (pinfunction "2_2") (pintype "passive"))
    )
    (net (code "63") (name "/cy_dq26") (class "Default")
      (node (ref "R72") (pin "4") (pinfunction "4_4") (pintype "passive"))
    )
    (net (code "64") (name "/cy_dq27") (class "Default")
      (node (ref "R63") (pin "1") (pinfunction "1_1") (pintype "passive"))
    )
    (net (code "65") (name "/cy_dq28") (class "Default")
      (node (ref "R66") (pin "1") (pinfunction "1_1") (pintype "passive"))
    )
    (net (code "66") (name "/cy_dq29") (class "Default")
      (node (ref "R73") (pin "3") (pinfunction "3_3") (pintype "passive"))
    )
    (net (code "67") (name "/cy_dq30") (class "Default")
      (node (ref "R74") (pin "4") (pinfunction "4_4") (pintype "passive"))
    )
    (net (code "68") (name "/cy_dq31") (class "Default")
      (node (ref "R73") (pin "4") (pinfunction "4_4") (pintype "passive"))
    )
    (net (code "69") (name "/cy_g") (class "Default")
      (node (ref "D10") (pin "D7") (pinfunction "CLKIN_D7") (pintype "passive"))
      (node (ref "VG1") (pin "3") (pinfunction "Out_3") (pintype "passive"))
    )
    (net (code "70") (name "/cy_pclk") (class "Default")
      (node (ref "R64") (pin "3") (pinfunction "3_3") (pintype "passive"))
    )
    (net (code "71") (name "/cy_scl") (class "Default")
      (node (ref "D10") (pin "D9") (pinfunction "I2C-GPIO58_SCL_D9") (pintype "output"))
      (node (ref "D11") (pin "6") (pinfunction "SCL_6") (pintype "input"))
      (node (ref "R75") (pin "1") (pinfunction "1_1") (pintype "passive"))
    )
    (net (code "72") (name "/cy_sda") (class "Default")
      (node (ref "D10") (pin "D10") (pinfunction "I2C-GPIO59_SDA_D10") (pintype "passive"))
      (node (ref "D11") (pin "5") (pinfunction "SDA_5") (pintype "bidirectional"))
      (node (ref "R76") (pin "1") (pinfunction "1_1") (pintype "passive"))
    )
    (net (code "73") (name "/d0") (class "Default")
      (node (ref "D10") (pin "F10") (pinfunction "DQ0_F10") (pintype "passive"))
      (node (ref "R74") (pin "6") (pinfunction "6_6") (pintype "passive"))
    )
    (net (code "74") (name "/d1") (class "Default")
      (node (ref "D10") (pin "F9") (pinfunction "DQ1_F9") (pintype "passive"))
      (node (ref "R67") (pin "6") (pinfunction "6_6") (pintype "passive"))
    )
    (net (code "75") (name "/d2") (class "Default")
      (node (ref "D10") (pin "F7") (pinfunction "DQ2_F7") (pintype "passive"))
      (node (ref "R67") (pin "8") (pinfunction "8_8") (pintype "passive"))
    )
    (net (code "76") (name "/d3") (class "Default")
      (node (ref "D10") (pin "G10") (pinfunction "DQ3_G10") (pintype "passive"))
      (node (ref "R74") (pin "7") (pinfunction "7_7") (pintype "passive"))
    )
    (net (code "77") (name "/d4") (class "Default")
      (node (ref "D10") (pin "G9") (pinfunction "DQ4_G9") (pintype "passive"))
      (node (ref "R65") (pin "6") (pinfunction "6_6") (pintype "passive"))
    )
    (net (code "78") (name "/d5") (class "Default")
      (node (ref "D10") (pin "F8") (pinfunction "DQ5_F8") (pintype "passive"))
      (node (ref "R67") (pin "7") (pinfunction "7_7") (pintype "passive"))
    )
    (net (code "79") (name "/d6") (class "Default")
      (node (ref "D10") (pin "H10") (pinfunction "DQ6_H10") (pintype "passive"))
      (node (ref "R74") (pin "8") (pinfunction "8_8") (pintype "passive"))
    )
    (net (code "80") (name "/d7") (class "Default")
      (node (ref "D10") (pin "H9") (pinfunction "DQ7_H9") (pintype "passive"))
      (node (ref "R65") (pin "7") (pinfunction "7_7") (pintype "passive"))
    )
    (net (code "81") (name "/d8") (class "Default")
      (node (ref "D10") (pin "J10") (pinfunction "DQ8_J10") (pintype "passive"))
      (node (ref "R58") (pin "5") (pinfunction "5_5") (pintype "passive"))
    )
    (net (code "82") (name "/d9") (class "Default")
      (node (ref "D10") (pin "J9") (pinfunction "DQ9_J9") (pintype "passive"))
      (node (ref "R71") (pin "7") (pinfunction "7_7") (pintype "passive"))
    )
    (net (code "83") (name "/d10") (class "Default")
      (node (ref "D10") (pin "K11") (pinfunction "DQ10_K11") (pintype "passive"))
      (node (ref "R58") (pin "6") (pinfunction "6_6") (pintype "passive"))
    )
    (net (code "84") (name "/d11") (class "Default")
      (node (ref "D10") (pin "L10") (pinfunction "DQ11_L10") (pintype "passive"))
      (node (ref "R58") (pin "8") (pinfunction "8_8") (pintype "passive"))
    )
    (net (code "85") (name "/d12") (class "Default")
      (node (ref "D10") (pin "K10") (pinfunction "DQ12_K10") (pintype "passive"))
      (node (ref "R58") (pin "7") (pinfunction "7_7") (pintype "passive"))
    )
    (net (code "86") (name "/d13") (class "Default")
      (node (ref "D10") (pin "K9") (pinfunction "DQ13_K9") (pintype "passive"))
      (node (ref "R69") (pin "5") (pinfunction "5_5") (pintype "passive"))
    )
    (net (code "87") (name "/d14") (class "Default")
      (node (ref "D10") (pin "J8") (pinfunction "DQ14_J8") (pintype "passive"))
      (node (ref "R71") (pin "6") (pinfunction "6_6") (pintype "passive"))
    )
    (net (code "88") (name "/d15") (class "Default")
      (node (ref "D10") (pin "G8") (pinfunction "DQ15_G8") (pintype "passive"))
      (node (ref "R65") (pin "5") (pinfunction "5_5") (pintype "passive"))
    )
    (net (code "89") (name "/d16") (class "Default")
      (node (ref "D10") (pin "K2") (pinfunction "DQ16_K2") (pintype "passive"))
      (node (ref "R70") (pin "6") (pinfunction "6_6") (pintype "passive"))
    )
    (net (code "90") (name "/d17") (class "Default")
      (node (ref "D10") (pin "J4") (pinfunction "DQ17_J4") (pintype "passive"))
      (node (ref "R66") (pin "5") (pinfunction "5_5") (pintype "passive"))
    )
    (net (code "91") (name "/d18") (class "Default")
      (node (ref "D10") (pin "K1") (pinfunction "DQ18_K1") (pintype "passive"))
      (node (ref "R70") (pin "7") (pinfunction "7_7") (pintype "passive"))
    )
    (net (code "92") (name "/d19") (class "Default")
      (node (ref "D10") (pin "J2") (pinfunction "DQ19_J2") (pintype "passive"))
      (node (ref "R70") (pin "8") (pinfunction "8_8") (pintype "passive"))
    )
    (net (code "93") (name "/d20") (class "Default")
      (node (ref "D10") (pin "J3") (pinfunction "DQ20_J3") (pintype "passive"))
      (node (ref "R72") (pin "8") (pinfunction "8_8") (pintype "passive"))
    )
    (net (code "94") (name "/d21") (class "Default")
      (node (ref "D10") (pin "J1") (pinfunction "DQ21_J1") (pintype "passive"))
      (node (ref "R63") (pin "5") (pinfunction "5_5") (pintype "passive"))
    )
    (net (code "95") (name "/d22") (class "Default")
      (node (ref "D10") (pin "H2") (pinfunction "DQ22_H2") (pintype "passive"))
      (node (ref "R63") (pin "6") (pinfunction "6_6") (pintype "passive"))
    )
    (net (code "96") (name "/d23") (class "Default")
      (node (ref "D10") (pin "H3") (pinfunction "DQ23_H3") (pintype "passive"))
      (node (ref "R72") (pin "6") (pinfunction "6_6") (pintype "passive"))
    )
    (net (code "97") (name "/d24") (class "Default")
      (node (ref "D10") (pin "F4") (pinfunction "DQ24_F4") (pintype "passive"))
      (node (ref "R72") (pin "7") (pinfunction "7_7") (pintype "passive"))
    )
    (net (code "98") (name "/d25") (class "Default")
      (node (ref "D10") (pin "G2") (pinfunction "DQ25_G2") (pintype "passive"))
      (node (ref "R63") (pin "7") (pinfunction "7_7") (pintype "passive"))
    )
    (net (code "99") (name "/d26") (class "Default")
      (node (ref "D10") (pin "G3") (pinfunction "DQ26_G3") (pintype "passive"))
      (node (ref "R72") (pin "5") (pinfunction "5_5") (pintype "passive"))
    )
    (net (code "100") (name "/d27") (class "Default")
      (node (ref "D10") (pin "F3") (pinfunction "DQ27_F3") (pintype "passive"))
      (node (ref "R63") (pin "8") (pinfunction "8_8") (pintype "passive"))
    )
    (net (code "101") (name "/d28") (class "Default")
      (node (ref "D10") (pin "F5") (pinfunction "DQ28_F5") (pintype "passive"))
      (node (ref "R66") (pin "8") (pinfunction "8_8") (pintype "passive"))
    )
    (net (code "102") (name "/d29") (class "Default")
      (node (ref "D10") (pin "E1") (pinfunction "DQ29_E1") (pintype "passive"))
      (node (ref "R73") (pin "6") (pinfunction "6_6") (pintype "passive"))
    )
    (net (code "103") (name "/d30") (class "Default")
      (node (ref "D10") (pin "E5") (pinfunction "DQ30_E5") (pintype "passive"))
      (node (ref "R74") (pin "5") (pinfunction "5_5") (pintype "passive"))
    )
    (net (code "104") (name "/d31") (class "Default")
      (node (ref "D10") (pin "E4") (pinfunction "DQ31_E4") (pintype "passive"))
      (node (ref "R73") (pin "5") (pinfunction "5_5") (pintype "passive"))
    )
    (net (code "105") (name "/ss_rx_N") (class "Default")
      (node (ref "D10") (pin "A3") (pinfunction "SSRXM_A3") (pintype "passive"))
      (node (ref "X4") (pin "8") (pinfunction "SSRx-_8") (pintype "passive"))
    )
    (net (code "106") (name "/ss_rx_P") (class "Default")
      (node (ref "D10") (pin "A4") (pinfunction "SSRXP_A4") (pintype "passive"))
      (node (ref "X4") (pin "9") (pinfunction "SSRx+_9") (pintype "passive"))
    )
    (net (code "107") (name "/ss_tx_N") (class "Default")
      (node (ref "C181") (pin "1") (pinfunction "1_1") (pintype "passive"))
      (node (ref "X4") (pin "5") (pinfunction "SSTx-_5") (pintype "passive"))
    )
    (net (code "108") (name "/ss_tx_P") (class "Default")
      (node (ref "C180") (pin "1") (pinfunction "1_1") (pintype "passive"))
      (node (ref "X4") (pin "6") (pinfunction "SSTx+_6") (pintype "passive"))
    )
    (net (code "109") (name "/usb_N") (class "Default")
      (node (ref "D10") (pin "A10") (pinfunction "DM_A10") (pintype "passive"))
      (node (ref "X4") (pin "2") (pinfunction "D-_2") (pintype "passive"))
    )
    (net (code "110") (name "/usb_P") (class "Default")
      (node (ref "D10") (pin "A9") (pinfunction "DP_A9") (pintype "passive"))
      (node (ref "X4") (pin "3") (pinfunction "D+_3") (pintype "passive"))
    )
    (net (code "111") (name "/v1p2d") (class "Default")
      (node (ref "C184") (pin "2") (pinfunction "2_2") (pintype "passive"))
      (node (ref "C192") (pin "2") (pinfunction "2_2") (pintype "passive"))
      (node (ref "C193") (pin "2") (pinfunction "2_2") (pintype "passive"))
      (node (ref "C194") (pin "2") (pinfunction "2_2") (pintype "passive"))
      (node (ref "C195") (pin "2") (pinfunction "2_2") (pintype "passive"))
      (node (ref "C196") (pin "2") (pinfunction "2_2") (pintype "passive"))
      (node (ref "C197") (pin "2") (pinfunction "2_2") (pintype "passive"))
      (node (ref "C198") (pin "2") (pinfunction "2_2") (pintype "passive"))
      (node (ref "C199") (pin "2") (pinfunction "2_2") (pintype "passive"))
      (node (ref "C200") (pin "2") (pinfunction "2_2") (pintype "passive"))
      (node (ref "C201") (pin "2") (pinfunction "2_2") (pintype "passive"))
      (node (ref "D10") (pin "B10") (pinfunction "VDD_EFVDDQ_B10") (pintype "passive"))
      (node (ref "D10") (pin "C3") (pinfunction "VDD2_C3") (pintype "passive"))
      (node (ref "D10") (pin "E9") (pinfunction "VDD4_E9") (pintype "passive"))
      (node (ref "D10") (pin "F11") (pinfunction "VDD5_F11") (pintype "passive"))
      (node (ref "D10") (pin "H1") (pinfunction "VDD1_H1") (pintype "passive"))
      (node (ref "D10") (pin "J11") (pinfunction "VDD_SRAM_VDD2_J11") (pintype "passive"))
      (node (ref "D10") (pin "L5") (pinfunction "VDD_SRAM_VDD1_L5") (pintype "passive"))
      (node (ref "D10") (pin "L7") (pinfunction "VDD3_L7") (pintype "passive"))
      (node (ref "D12") (pin "10") (pinfunction "Vout_10") (pintype "passive"))
      (node (ref "D12") (pin "11") (pinfunction "Vout_11") (pintype "passive"))
      (node (ref "D12") (pin "12") (pinfunction "Vout_12") (pintype "passive"))
      (node (ref "D12") (pin "13") (pinfunction "Vout_13") (pintype "passive"))
      (node (ref "D12") (pin "14") (pinfunction "Vout_14") (pintype "passive"))
      (node (ref "L10") (pin "1") (pinfunction "1_1") (pintype "passive"))
      (node (ref "L11") (pin "1") (pinfunction "1_1") (pintype "passive"))
      (node (ref "L12") (pin "1") (pinfunction "1_1") (pintype "passive"))
      (node (ref "R82") (pin "2") (pinfunction "2_2") (pintype "passive"))
    )
    (net (code "112") (name "/v1p8d") (class "Default")
      (node (ref "C202") (pin "2") (pinfunction "2_2") (pintype "passive"))
      (node (ref "C203") (pin "2") (pinfunction "2_2") (pintype "passive"))
      (node (ref "C204") (pin "2") (pinfunction "2_2") (pintype "passive"))
      (node (ref "C205") (pin "2") (pinfunction "2_2") (pintype "passive"))
      (node (ref "C206") (pin "2") (pinfunction "2_2") (pintype "passive"))
      (node (ref "C207") (pin "2") (pinfunction "2_2") (pintype "passive"))
      (node (ref "C208") (pin "2") (pinfunction "2_2") (pintype "passive"))
      (node (ref "D10") (pin "B1") (pinfunction "VIO4_B1") (pintype "passive"))
      (node (ref "D10") (pin "E3") (pinfunction "VIO3_E3") (pintype "passive"))
      (node (ref "D10") (pin "F1") (pinfunction "VIO2_F1") (pintype "passive"))
      (node (ref "D10") (pin "H11") (pinfunction "VIO1_2_H11") (pintype "passive"))
      (node (ref "D10") (pin "L9") (pinfunction "VIO1_1_L9") (pintype "passive"))
      (node (ref "D12") (pin "1") (pinfunction "Vin_1") (pintype "passive"))
      (node (ref "D12") (pin "15") (pinfunction "Vin_15") (pintype "passive"))
      (node (ref "D12") (pin "16") (pinfunction "Vin_16") (pintype "passive"))
      (node (ref "D12") (pin "2") (pinfunction "Vin_2") (pintype "passive"))
      (node (ref "D12") (pin "3") (pinfunction "Vin_3") (pintype "passive"))
      (node (ref "D12") (pin "4") (pinfunction "EN_4") (pintype "passive"))
      (node (ref "R77") (pin "2") (pinfunction "2_2") (pintype "passive"))
      (node (ref "R78") (pin "2") (pinfunction "2_2") (pintype "passive"))
      (node (ref "R81") (pin "2") (pinfunction "2_2") (pintype "passive"))
      (node (ref "R84") (pin "2") (pinfunction "2_2") (pintype "passive"))
    )
    (net (code "113") (name "/v3p3d") (class "Default")
      (node (ref "C209") (pin "2") (pinfunction "2_2") (pintype "passive"))
      (node (ref "C210") (pin "2") (pinfunction "2_2") (pintype "passive"))
      (node (ref "C211") (pin "2") (pinfunction "2_2") (pintype "passive"))
      (node (ref "C212") (pin "2") (pinfunction "2_2") (pintype "passive"))
      (node (ref "C213") (pin "2") (pinfunction "2_2") (pintype "passive"))
      (node (ref "C214") (pin "2") (pinfunction "2_2") (pintype "passive"))
      (node (ref "D10") (pin "B6") (pinfunction "CVDDQ_B6") (pintype "passive"))
      (node (ref "D10") (pin "C11") (pinfunction "VIO5_C11") (pintype "passive"))
      (node (ref "D10") (pin "E10") (pinfunction "VBAT_E10") (pintype "passive"))
      (node (ref "D11") (pin "8") (pinfunction "VCC_8") (pintype "power_in"))
      (node (ref "R108") (pin "1") (pinfunction "1_1") (pintype "passive"))
      (node (ref "R62") (pin "1") (pinfunction "1_1") (pintype "passive"))
      (node (ref "R75") (pin "2") (pinfunction "2_2") (pintype "passive"))
      (node (ref "R76") (pin "2") (pinfunction "2_2") (pintype "passive"))
      (node (ref "VG1") (pin "4") (pinfunction "Vcc_4") (pintype "passive"))
    )
    (net (code "114") (name "Net-(D10A-INT_N_CTL15)") (class "Default")
      (node (ref "D10") (pin "L8") (pinfunction "INT_N_CTL15_L8") (pintype "passive"))
      (node (ref "R80") (pin "1") (pinfunction "1_1") (pintype "passive"))
    )
    (net (code "115") (name "Net-(D10A-PMODE0)") (class "Default")
      (node (ref "D10") (pin "G4") (pinfunction "PMODE0_G4") (pintype "passive"))
      (node (ref "R77") (pin "1") (pinfunction "1_1") (pintype "passive"))
    )
    (net (code "116") (name "Net-(D10A-PMODE1)") (class "Default")
      (node (ref "D10") (pin "H4") (pinfunction "PMODE1_H4") (pintype "passive"))
      (node (ref "R78") (pin "1") (pinfunction "1_1") (pintype "passive"))
    )
    (net (code "117") (name "Net-(D10A-PMODE2)") (class "Default")
      (node (ref "D10") (pin "L4") (pinfunction "PMODE2_L4") (pintype "passive"))
      (node (ref "R79") (pin "1") (pinfunction "1_1") (pintype "passive"))
    )
    (net (code "118") (name "Net-(D10A-RESET_N)") (class "Default")
      (node (ref "C187") (pin "2") (pinfunction "2_2") (pintype "passive"))
      (node (ref "D10") (pin "C5") (pinfunction "RESET_N_C5") (pintype "passive"))
      (node (ref "R81") (pin "1") (pinfunction "1_1") (pintype "passive"))
    )
    (net (code "119") (name "Net-(D10D-OTG_ID)") (class "Default")
      (node (ref "D10") (pin "C9") (pinfunction "OTG_ID_C9") (pintype "passive"))
      (node (ref "R60") (pin "1") (pinfunction "1_1") (pintype "passive"))
    )
    (net (code "120") (name "Net-(D10D-R_USB2)") (class "Default")
      (node (ref "D10") (pin "C8") (pinfunction "R_USB2_C8") (pintype "passive"))
      (node (ref "R109") (pin "1") (pinfunction "1_1") (pintype "passive"))
    )
    (net (code "121") (name "Net-(D10D-R_USB3)") (class "Default")
      (node (ref "D10") (pin "B3") (pinfunction "R_USB3_B3") (pintype "passive"))
      (node (ref "R68") (pin "1") (pinfunction "1_1") (pintype "passive"))
    )
    (net (code "122") (name "Net-(D10D-SSTXM)") (class "Default")
      (node (ref "C181") (pin "2") (pinfunction "2_2") (pintype "passive"))
      (node (ref "D10") (pin "A6") (pinfunction "SSTXM_A6") (pintype "passive"))
    )
    (net (code "123") (name "Net-(D10D-SSTXP)") (class "Default")
      (node (ref "C180") (pin "2") (pinfunction "2_2") (pintype "passive"))
      (node (ref "D10") (pin "A5") (pinfunction "SSTXP_A5") (pintype "passive"))
    )
    (net (code "124") (name "Net-(D10D-VBUS)") (class "Default")
      (node (ref "C179") (pin "1") (pinfunction "1_1") (pintype "passive"))
      (node (ref "D10") (pin "E11") (pinfunction "VBUS_E11") (pintype "passive"))
      (node (ref "R57") (pin "1") (pinfunction "1_1") (pintype "passive"))
    )
    (net (code "125") (name "Net-(D10E-FSLC0)") (class "Default")
      (node (ref "D10") (pin "B2") (pinfunction "FSLC0_B2") (pintype "passive"))
      (node (ref "R59") (pin "2") (pinfunction "2_2") (pintype "passive"))
    )
    (net (code "126") (name "Net-(D10E-FSLC1)") (class "Default")
      (node (ref "D10") (pin "B4") (pinfunction "FSLC1_B4") (pintype "passive"))
      (node (ref "R61") (pin "2") (pinfunction "2_2") (pintype "passive"))
    )
    (net (code "127") (name "Net-(D10E-FSLC2)") (class "Default")
      (node (ref "D10") (pin "E6") (pinfunction "FSLC2_E6") (pintype "passive"))
      (node (ref "R62") (pin "2") (pinfunction "2_2") (pintype "passive"))
    )
    (net (code "128") (name "Net-(D10E-XTALIN)") (class "Default")
      (node (ref "C183") (pin "2") (pinfunction "2_2") (pintype "passive"))
      (node (ref "D10") (pin "C6") (pinfunction "XTALIN_C6") (pintype "passive"))
      (node (ref "ZQ1") (pin "2") (pinfunction "2_2") (pintype "passive"))
    )
    (net (code "129") (name "Net-(D10E-XTALOUT)") (class "Default")
      (node (ref "C182") (pin "2") (pinfunction "2_2") (pintype "passive"))
      (node (ref "D10") (pin "C7") (pinfunction "XTALOUT_C7") (pintype "passive"))
      (node (ref "ZQ1") (pin "1") (pinfunction "1_1") (pintype "passive"))
    )
    (net (code "130") (name "Net-(D12-Adj)") (class "Default")
      (node (ref "D12") (pin "9") (pinfunction "Adj_9") (pintype "passive"))
      (node (ref "R82") (pin "1") (pinfunction "1_1") (pintype "passive"))
      (node (ref "R83") (pin "2") (pinfunction "2_2") (pintype "passive"))
    )
    (net (code "131") (name "Net-(D12-PG)") (class "Default")
      (node (ref "D12") (pin "5") (pinfunction "PG_5") (pintype "passive"))
      (node (ref "R84") (pin "1") (pinfunction "1_1") (pintype "passive"))
    )
    (net (code "132") (name "Net-(VG1-EN)") (class "Default")
      (node (ref "R108") (pin "2") (pinfunction "2_2") (pintype "passive"))
      (node (ref "VG1") (pin "1") (pinfunction "EN_1") (pintype "passive"))
    )
    (net (code "133") (name "Net-(X4-VBUS)") (class "Default")
      (node (ref "R57") (pin "2") (pinfunction "2_2") (pintype "passive"))
      (node (ref "X4") (pin "1") (pinfunction "VBUS_1") (pintype "passive"))
    )
    (net (code "134") (name "unconnected-(D10B-GPIO45-PadF2)") (class "Default")
      (node (ref "D10") (pin "F2") (pinfunction "GPIO45_F2") (pintype "passive"))
    )
    (net (code "135") (name "unconnected-(D10C-I2S-CLK-PadD1)") (class "Default")
      (node (ref "D10") (pin "D1") (pinfunction "I2S-CLK_D1") (pintype "passive"))
    )
    (net (code "136") (name "unconnected-(D10C-I2S-MCLK-PadC4)") (class "Default")
      (node (ref "D10") (pin "C4") (pinfunction "I2S-MCLK_C4") (pintype "passive"))
    )
    (net (code "137") (name "unconnected-(D10C-UART-TX_SPI-MISO-PadC2)") (class "Default")
      (node (ref "D10") (pin "C2") (pinfunction "UART-TX_SPI-MISO_C2") (pintype "passive"))
    )
    (net (code "138") (name "unconnected-(D10D-NC-PadA11)") (class "Default")
      (node (ref "D10") (pin "A11") (pinfunction "NC_A11") (pintype "passive"))
    )
    (net (code "139") (name "unconnected-(D10E-CLKIN_32-PadD6)") (class "Default")
      (node (ref "D10") (pin "D6") (pinfunction "CLKIN_32_D6") (pintype "passive"))
    )
    (net (code "140") (name "unconnected-(D10F-I2C-GPIO60_CHARGER-DETECT-PadD11)") (class "Default")
      (node (ref "D10") (pin "D11") (pinfunction "I2C-GPIO60_CHARGER-DETECT_D11") (pintype "passive"))
    )
    (net (code "141") (name "unconnected-(D10F-TCK-PadF6)") (class "Default")
      (node (ref "D10") (pin "F6") (pinfunction "TCK_F6") (pintype "passive"))
    )
    (net (code "142") (name "unconnected-(D10F-TDI-PadE7)") (class "Default")
      (node (ref "D10") (pin "E7") (pinfunction "TDI_E7") (pintype "passive"))
    )
    (net (code "143") (name "unconnected-(D10F-TDO-PadC10)") (class "Default")
      (node (ref "D10") (pin "C10") (pinfunction "TDO_C10") (pintype "passive"))
    )
    (net (code "144") (name "unconnected-(D10F-TMS-PadE8)") (class "Default")
      (node (ref "D10") (pin "E8") (pinfunction "TMS_E8") (pintype "passive"))
    )
    (net (code "145") (name "unconnected-(D10F-TRST_N-PadB11)") (class "Default")
      (node (ref "D10") (pin "B11") (pinfunction "TRST_N_B11") (pintype "passive"))
    )
    (net (code "146") (name "unconnected-(D12-NC-Pad8)") (class "Default")
      (node (ref "D12") (pin "8") (pinfunction "NC_8") (pintype "passive"))
    )
    (net (code "147") (name "unconnected-(D12-SS-Pad7)") (class "Default")
      (node (ref "D12") (pin "7") (pinfunction "SS_7") (pintype "passive"))
    )
    (net (code "148") (name "unconnected-(R73-Pad1)") (class "Default")
      (node (ref "R73") (pin "1") (pinfunction "1_1") (pintype "passive"))
    )
    (net (code "149") (name "unconnected-(R73-Pad2)") (class "Default")
      (node (ref "R73") (pin "2") (pinfunction "2_2") (pintype "passive"))
    )
    (net (code "150") (name "unconnected-(R73-Pad7)") (class "Default")
      (node (ref "R73") (pin "7") (pinfunction "7_7") (pintype "passive"))
    )
    (net (code "151") (name "unconnected-(R73-Pad8)") (class "Default")
      (node (ref "R73") (pin "8") (pinfunction "8_8") (pintype "passive"))
    )
  )
)
